# OpenEVSE_PLUS_v2_30a.net
KiCad netlist of a schematic drawn in EAGLE
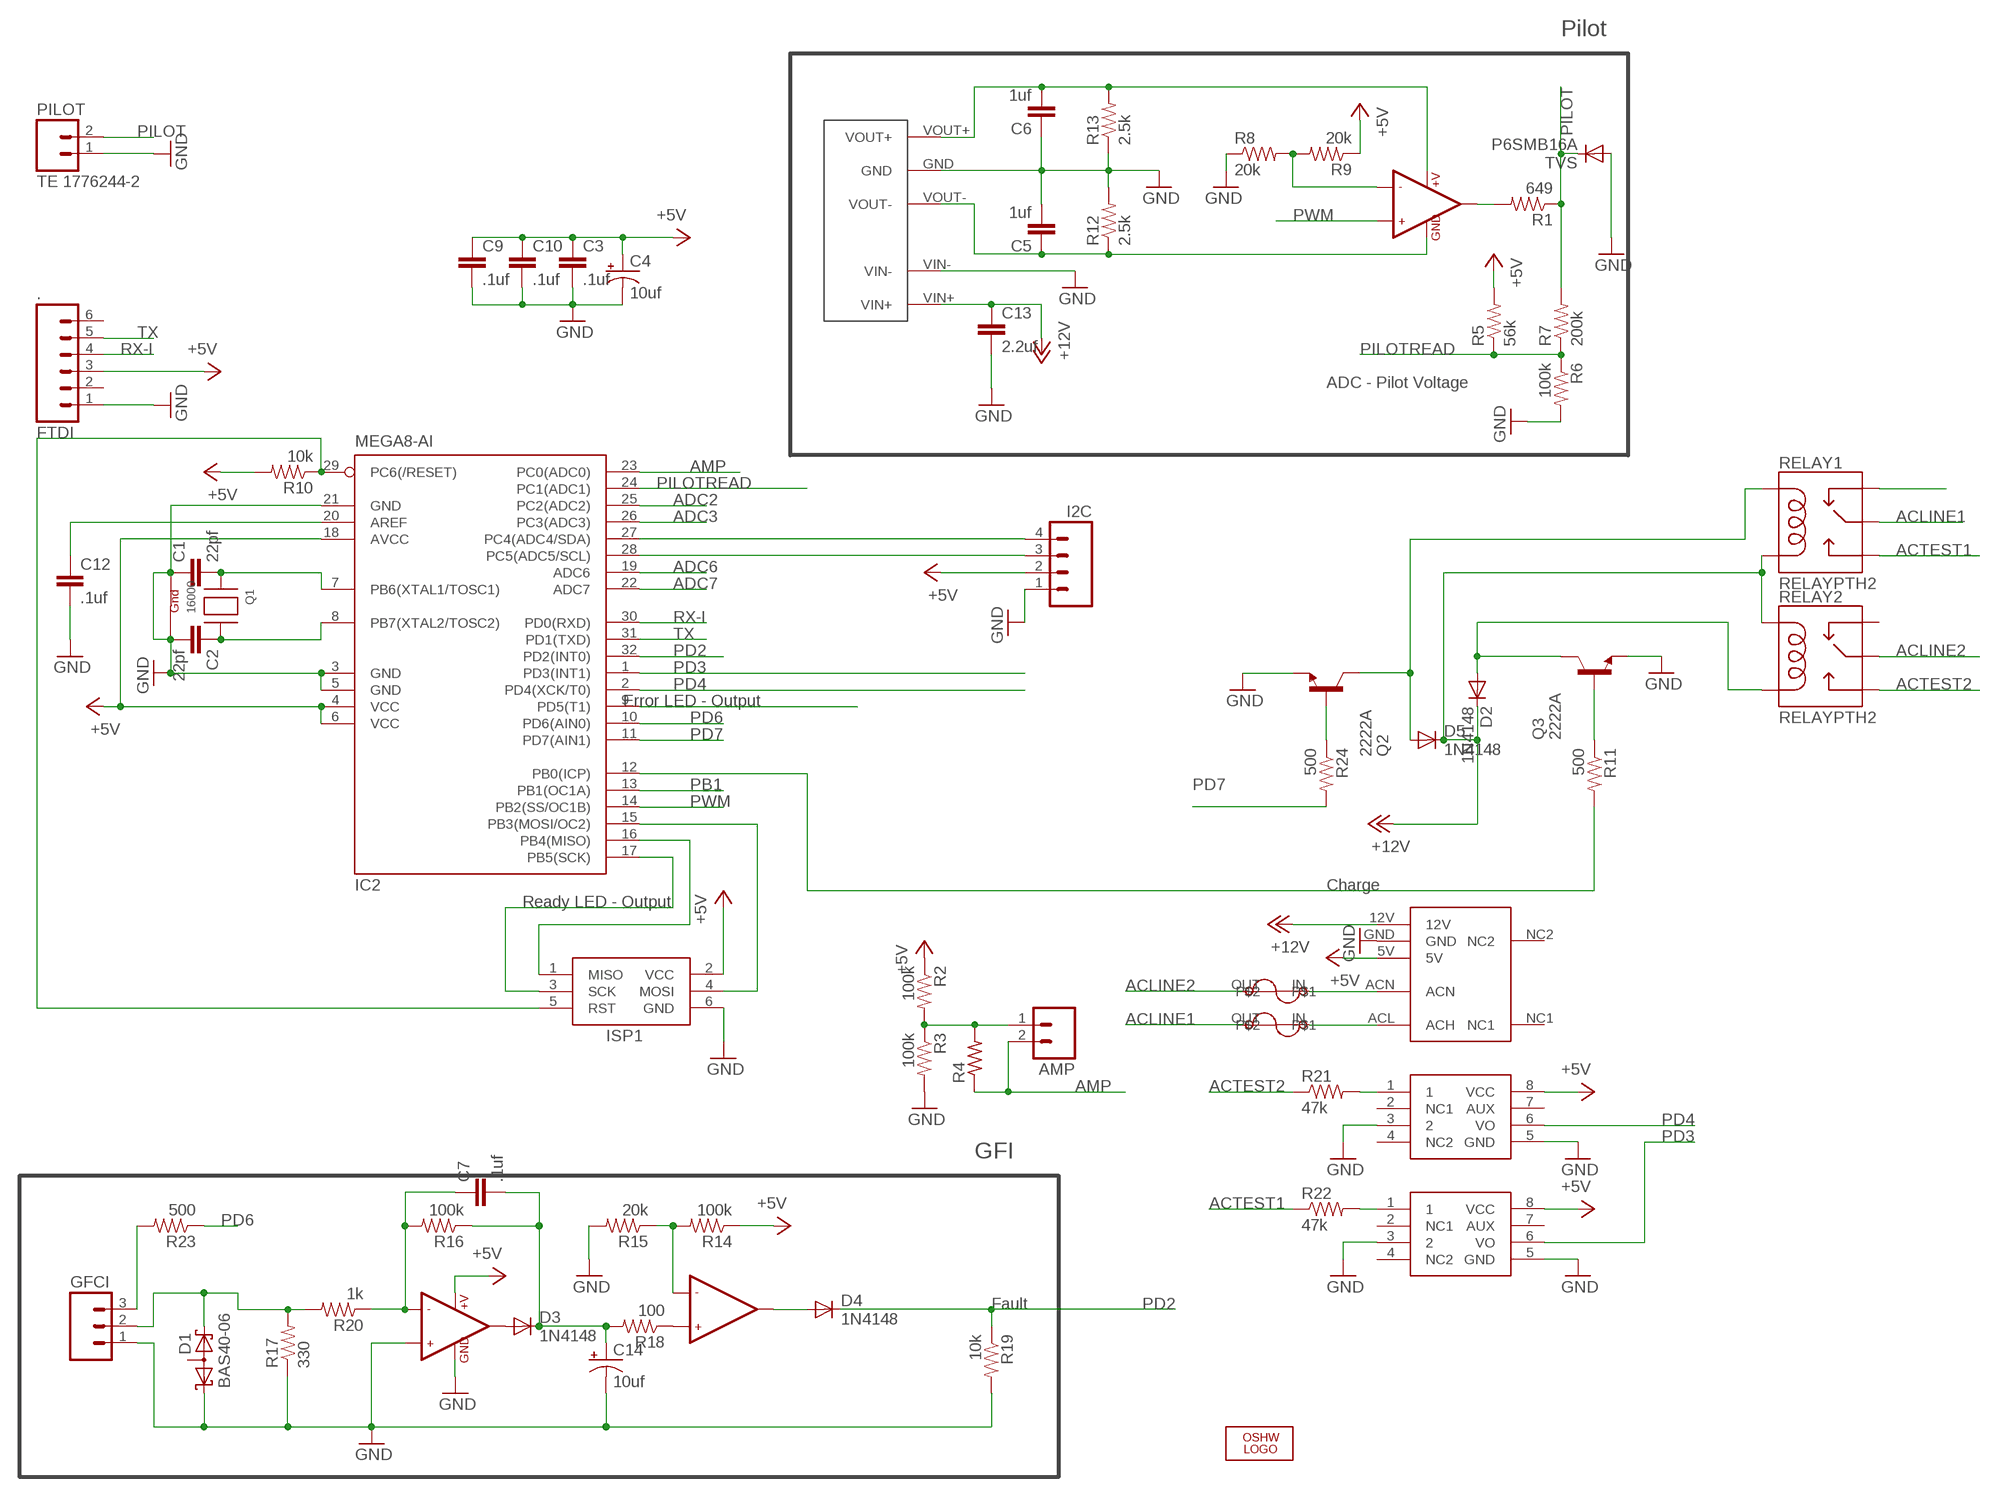
[diagram p0: schematic, sheet 1]

(export (version "E")
  (design (tool "Eeschema 10.0.6"))
  (components
    (comp (ref ".")
      (value "FTDI")
      (footprint "eagle-import:1X06_LOCK")
      (libsource (lib "eagle-import") (part "M06LOCK"))
    )
    (comp (ref "AMP")
      (value "M02LOCK")
      (footprint "eagle-import:1X02_LOCK")
      (libsource (lib "eagle-import") (part "M02LOCK"))
    )
    (comp (ref "C1")
      (value "22pf")
      (footprint "eagle-import:0805")
      (libsource (lib "eagle-import") (part "CAP0805"))
    )
    (comp (ref "C2")
      (value "22pf")
      (footprint "eagle-import:0805")
      (libsource (lib "eagle-import") (part "CAP0805"))
    )
    (comp (ref "C3")
      (value ".1uf")
      (footprint "eagle-import:0805")
      (libsource (lib "eagle-import") (part "CAP0805"))
    )
    (comp (ref "C4")
      (value "10uf")
      (footprint "eagle-import:EIA3216")
      (libsource (lib "eagle-import") (part "CAP_POL1206"))
    )
    (comp (ref "C5")
      (value "1uf")
      (footprint "eagle-import:0805")
      (libsource (lib "eagle-import") (part "CAP0805"))
    )
    (comp (ref "C6")
      (value "1uf")
      (footprint "eagle-import:0805")
      (libsource (lib "eagle-import") (part "CAP0805"))
    )
    (comp (ref "C7")
      (value ".1uf")
      (footprint "eagle-import:0805")
      (libsource (lib "eagle-import") (part "CAP0805"))
    )
    (comp (ref "C9")
      (value ".1uf")
      (footprint "eagle-import:0805")
      (libsource (lib "eagle-import") (part "CAP0805"))
    )
    (comp (ref "C10")
      (value ".1uf")
      (footprint "eagle-import:0805")
      (libsource (lib "eagle-import") (part "CAP0805"))
    )
    (comp (ref "C12")
      (value ".1uf")
      (footprint "eagle-import:0805")
      (libsource (lib "eagle-import") (part "CAP0805"))
    )
    (comp (ref "C13")
      (value "2.2uf")
      (footprint "eagle-import:0805")
      (libsource (lib "eagle-import") (part "CAP0805"))
    )
    (comp (ref "C14")
      (value "10uf")
      (footprint "eagle-import:EIA3216")
      (libsource (lib "eagle-import") (part "CAP_POL1206"))
    )
    (comp (ref "D1")
      (value "BAS40-06")
      (footprint "eagle-import:SOT23")
      (libsource (lib "eagle-import") (part "BAS40-06"))
    )
    (comp (ref "D2")
      (value "1N4148")
      (footprint "eagle-import:SOD123")
      (libsource (lib "eagle-import") (part "DIODE-SOD123"))
    )
    (comp (ref "D3")
      (value "1N4148")
      (footprint "eagle-import:SOD123")
      (libsource (lib "eagle-import") (part "DIODE-SOD123"))
    )
    (comp (ref "D4")
      (value "1N4148")
      (footprint "eagle-import:SOD123")
      (libsource (lib "eagle-import") (part "DIODE-SOD123"))
    )
    (comp (ref "D5")
      (value "1N4148")
      (footprint "eagle-import:SOD123")
      (libsource (lib "eagle-import") (part "DIODE-SOD123"))
    )
    (comp (ref "DCDC")
      (value "D107E")
      (footprint "eagle-import:DCDC_SIP")
      (libsource (lib "eagle-import") (part "DCDC_SIP"))
    )
    (comp (ref "GFCI")
      (value "M03LOCK")
      (footprint "eagle-import:1X03_LOCK")
      (libsource (lib "eagle-import") (part "M03LOCK"))
    )
    (comp (ref "I2C")
      (value "M04LOCK")
      (footprint "eagle-import:1X04_LOCK")
      (libsource (lib "eagle-import") (part "M04LOCK"))
    )
    (comp (ref "IC1")
      (value "MID400")
      (footprint "eagle-import:DIP08")
      (libsource (lib "eagle-import") (part "MID400"))
    )
    (comp (ref "IC2")
      (value "MEGA8-AI")
      (footprint "eagle-import:TQFP32-08")
      (fields (field (name "MPN") "ATMEGA8-16AU"))
      (libsource (lib "eagle-import") (part "MEGA8-AI"))
    )
    (comp (ref "IC3")
      (value "LMV358")
      (footprint "eagle-import:SO08")
      (libsource (lib "eagle-import") (part "LMV358"))
    )
    (comp (ref "IC4")
      (value "LMV358")
      (footprint "eagle-import:SO08")
      (libsource (lib "eagle-import") (part "LMV358"))
    )
    (comp (ref "IC5")
      (value "MID400")
      (footprint "eagle-import:DIP08")
      (libsource (lib "eagle-import") (part "MID400"))
    )
    (comp (ref "ISP1")
      (value "AVRISP-6")
      (footprint "eagle-import:AVRISP")
      (libsource (lib "eagle-import") (part "AVRISP-6"))
    )
    (comp (ref "LOGO1")
      (value "OSHW_LOGO_8MILX0150-NT")
      (footprint "eagle-import:OSHW_8X150_NOTEXT")
      (libsource (lib "eagle-import") (part "OSHW_LOGO_8MILX0150-NT"))
    )
    (comp (ref "PILOT")
      (value "TE 1776244-2")
      (footprint "eagle-import:SCREWTERMINAL-5MM-2")
      (libsource (lib "eagle-import") (part "M025MM"))
    )
    (comp (ref "Q1")
      (value "16000")
      (footprint "eagle-import:NX3225")
      (libsource (lib "eagle-import") (part "XTAL-4-3225"))
    )
    (comp (ref "Q2")
      (value "2222A")
      (footprint "eagle-import:SOT23")
      (libsource (lib "eagle-import") (part "BCX70SMD"))
    )
    (comp (ref "Q3")
      (value "2222A")
      (footprint "eagle-import:SOT23")
      (libsource (lib "eagle-import") (part "BCX70SMD"))
    )
    (comp (ref "R1")
      (value "649")
      (footprint "eagle-import:0805")
      (libsource (lib "eagle-import") (part "RESISTOR0805-RES"))
    )
    (comp (ref "R2")
      (value "100k")
      (footprint "eagle-import:0805")
      (libsource (lib "eagle-import") (part "RESISTOR0805-RES"))
    )
    (comp (ref "R3")
      (value "100k")
      (footprint "eagle-import:0805")
      (libsource (lib "eagle-import") (part "RESISTOR0805-RES"))
    )
    (comp (ref "R4")
      (value "R-US_0207/2V")
      (footprint "eagle-import:0207_2V")
      (libsource (lib "eagle-import") (part "R-US_0207/2V"))
    )
    (comp (ref "R5")
      (value "56k")
      (footprint "eagle-import:0805")
      (libsource (lib "eagle-import") (part "RESISTOR0805-RES"))
    )
    (comp (ref "R6")
      (value "100k")
      (footprint "eagle-import:0805")
      (libsource (lib "eagle-import") (part "RESISTOR0805-RES"))
    )
    (comp (ref "R7")
      (value "200k")
      (footprint "eagle-import:0805")
      (libsource (lib "eagle-import") (part "RESISTOR0805-RES"))
    )
    (comp (ref "R8")
      (value "20k")
      (footprint "eagle-import:0805")
      (libsource (lib "eagle-import") (part "RESISTOR0805-RES"))
    )
    (comp (ref "R9")
      (value "20k")
      (footprint "eagle-import:0805")
      (libsource (lib "eagle-import") (part "RESISTOR0805-RES"))
    )
    (comp (ref "R10")
      (value "10k")
      (footprint "eagle-import:0805")
      (libsource (lib "eagle-import") (part "RESISTOR0805-RES"))
    )
    (comp (ref "R11")
      (value "500")
      (footprint "eagle-import:0805")
      (libsource (lib "eagle-import") (part "RESISTOR0805-RES"))
    )
    (comp (ref "R12")
      (value "2.5k")
      (footprint "eagle-import:0805")
      (libsource (lib "eagle-import") (part "RESISTOR0805-RES"))
    )
    (comp (ref "R13")
      (value "2.5k")
      (footprint "eagle-import:0805")
      (libsource (lib "eagle-import") (part "RESISTOR0805-RES"))
    )
    (comp (ref "R14")
      (value "100k")
      (footprint "eagle-import:0805")
      (libsource (lib "eagle-import") (part "RESISTOR0805-RES"))
    )
    (comp (ref "R15")
      (value "20k")
      (footprint "eagle-import:0805")
      (libsource (lib "eagle-import") (part "RESISTOR0805-RES"))
    )
    (comp (ref "R16")
      (value "100k")
      (footprint "eagle-import:0805")
      (libsource (lib "eagle-import") (part "RESISTOR0805-RES"))
    )
    (comp (ref "R17")
      (value "330")
      (footprint "eagle-import:0805")
      (libsource (lib "eagle-import") (part "RESISTOR0805-RES"))
    )
    (comp (ref "R18")
      (value "100")
      (footprint "eagle-import:0805")
      (libsource (lib "eagle-import") (part "RESISTOR0805-RES"))
    )
    (comp (ref "R19")
      (value "10k")
      (footprint "eagle-import:0805")
      (libsource (lib "eagle-import") (part "RESISTOR0805-RES"))
    )
    (comp (ref "R20")
      (value "1k")
      (footprint "eagle-import:0805")
      (libsource (lib "eagle-import") (part "RESISTOR0805-RES"))
    )
    (comp (ref "R21")
      (value "47k")
      (footprint "eagle-import:AXIAL-0.4")
      (libsource (lib "eagle-import") (part "RESISTORPTH-1/4W"))
    )
    (comp (ref "R22")
      (value "47k")
      (footprint "eagle-import:AXIAL-0.4")
      (libsource (lib "eagle-import") (part "RESISTORPTH-1/4W"))
    )
    (comp (ref "R23")
      (value "500")
      (footprint "eagle-import:0805")
      (libsource (lib "eagle-import") (part "RESISTOR0805-RES"))
    )
    (comp (ref "R24")
      (value "500")
      (footprint "eagle-import:0805")
      (libsource (lib "eagle-import") (part "RESISTOR0805-RES"))
    )
    (comp (ref "RELAY1")
      (value "RELAYPTH2")
      (footprint "eagle-import:RELAY-T9A")
      (libsource (lib "eagle-import") (part "RELAYPTH2"))
    )
    (comp (ref "RELAY2")
      (value "RELAYPTH2")
      (footprint "eagle-import:RELAY-T9A")
      (libsource (lib "eagle-import") (part "RELAYPTH2"))
    )
    (comp (ref "TVS")
      (value "P6SMB16A")
      (footprint "eagle-import:SMB")
      (libsource (lib "eagle-import") (part "DIODE-SMB"))
    )
    (comp (ref "U$1")
      (value "MPM-04E-1205")
      (footprint "eagle-import:MPM-04E-1205")
      (libsource (lib "eagle-import") (part "MPM-04E-1205"))
    )
    (comp (ref "U$2")
      (value "BEL1AFUSE")
      (footprint "eagle-import:BELFUSE1A")
      (libsource (lib "eagle-import") (part "BEL1AFUSE"))
    )
    (comp (ref "U$5")
      (value "BEL1AFUSE")
      (footprint "eagle-import:BELFUSE1A")
      (libsource (lib "eagle-import") (part "BEL1AFUSE"))
    )
  )
  (nets
    (net (code "1") (name "+5V") (class "Default")
      (node (ref ".") (pin "3") (pinfunction "3_3") (pintype "passive"))
      (node (ref "C10") (pin "1") (pinfunction "1_1") (pintype "passive"))
      (node (ref "C3") (pin "1") (pinfunction "1_1") (pintype "passive"))
      (node (ref "C4") (pin "A") (pinfunction "+_A") (pintype "passive"))
      (node (ref "C9") (pin "1") (pinfunction "1_1") (pintype "passive"))
      (node (ref "I2C") (pin "2") (pinfunction "2_2") (pintype "passive"))
      (node (ref "IC1") (pin "8") (pinfunction "VCC_8") (pintype "bidirectional"))
      (node (ref "IC2") (pin "18") (pinfunction "AVCC_18") (pintype "power_in"))
      (node (ref "IC2") (pin "4") (pinfunction "VCC_4") (pintype "power_in"))
      (node (ref "IC2") (pin "6") (pinfunction "VCC_6") (pintype "power_in"))
      (node (ref "IC3") (pin "8") (pinfunction "+V_8") (pintype "power_in"))
      (node (ref "IC5") (pin "8") (pinfunction "VCC_8") (pintype "bidirectional"))
      (node (ref "ISP1") (pin "2") (pinfunction "VCC_2") (pintype "power_in"))
      (node (ref "R10") (pin "2") (pinfunction "2_2") (pintype "passive"))
      (node (ref "R14") (pin "1") (pinfunction "1_1") (pintype "passive"))
      (node (ref "R2") (pin "1") (pinfunction "1_1") (pintype "passive"))
      (node (ref "R5") (pin "2") (pinfunction "2_2") (pintype "passive"))
      (node (ref "R9") (pin "1") (pinfunction "1_1") (pintype "passive"))
      (node (ref "U$1") (pin "5V") (pinfunction "5V_5V") (pintype "bidirectional"))
    )
    (net (code "2") (name "+12V") (class "Default")
      (node (ref "C13") (pin "1") (pinfunction "1_1") (pintype "passive"))
      (node (ref "D2") (pin "C") (pinfunction "C_C") (pintype "passive"))
      (node (ref "D5") (pin "C") (pinfunction "C_C") (pintype "passive"))
      (node (ref "DCDC") (pin "VIN+") (pinfunction "VIN+_VIN+") (pintype "bidirectional"))
      (node (ref "RELAY1") (pin "COIL2") (pinfunction "COIL2_COIL2") (pintype "bidirectional"))
      (node (ref "RELAY2") (pin "COIL1") (pinfunction "COIL1_COIL1") (pintype "bidirectional"))
      (node (ref "U$1") (pin "12V") (pinfunction "12V_12V") (pintype "bidirectional"))
    )
    (net (code "3") (name "/ACLINE1") (class "Default")
      (node (ref "RELAY1") (pin "MAIN") (pinfunction "MAIN_MAIN") (pintype "bidirectional"))
      (node (ref "U$2") (pin "OUT") (pinfunction "P$1_OUT") (pintype "bidirectional"))
    )
    (net (code "4") (name "/ACLINE2") (class "Default")
      (node (ref "RELAY2") (pin "MAIN") (pinfunction "MAIN_MAIN") (pintype "bidirectional"))
      (node (ref "U$5") (pin "OUT") (pinfunction "P$1_OUT") (pintype "bidirectional"))
    )
    (net (code "5") (name "/ACTEST1") (class "Default")
      (node (ref "R22") (pin "P$1") (pinfunction "1_P$1") (pintype "passive"))
      (node (ref "RELAY1") (pin "NO") (pinfunction "NO_NO") (pintype "bidirectional"))
    )
    (net (code "6") (name "/ACTEST2") (class "Default")
      (node (ref "R21") (pin "P$1") (pinfunction "1_P$1") (pintype "passive"))
      (node (ref "RELAY2") (pin "NO") (pinfunction "NO_NO") (pintype "bidirectional"))
    )
    (net (code "7") (name "/ADC2") (class "Default")
      (node (ref "IC2") (pin "25") (pinfunction "PC2(ADC2)_25") (pintype "bidirectional"))
    )
    (net (code "8") (name "/ADC3") (class "Default")
      (node (ref "IC2") (pin "26") (pinfunction "PC3(ADC3)_26") (pintype "bidirectional"))
    )
    (net (code "9") (name "/ADC6") (class "Default")
      (node (ref "IC2") (pin "19") (pinfunction "ADC6_19") (pintype "bidirectional"))
    )
    (net (code "10") (name "/ADC7") (class "Default")
      (node (ref "IC2") (pin "22") (pinfunction "ADC7_22") (pintype "bidirectional"))
    )
    (net (code "11") (name "/AMP") (class "Default")
      (node (ref "AMP") (pin "2") (pinfunction "2_2") (pintype "passive"))
      (node (ref "IC2") (pin "23") (pinfunction "PC0(ADC0)_23") (pintype "bidirectional"))
      (node (ref "R4") (pin "1") (pinfunction "1_1") (pintype "passive"))
    )
    (net (code "12") (name "/PB1") (class "Default")
      (node (ref "IC2") (pin "13") (pinfunction "PB1(OC1A)_13") (pintype "bidirectional"))
    )
    (net (code "13") (name "/PD2") (class "Default")
      (node (ref "D4") (pin "C") (pinfunction "C_C") (pintype "passive"))
      (node (ref "IC2") (pin "32") (pinfunction "PD2(INT0)_32") (pintype "bidirectional"))
      (node (ref "R19") (pin "1") (pinfunction "1_1") (pintype "passive"))
    )
    (net (code "14") (name "/PD3") (class "Default")
      (node (ref "IC2") (pin "1") (pinfunction "PD3(INT1)_1") (pintype "bidirectional"))
      (node (ref "IC5") (pin "6") (pinfunction "VO_6") (pintype "bidirectional"))
    )
    (net (code "15") (name "/PD4") (class "Default")
      (node (ref "IC1") (pin "6") (pinfunction "VO_6") (pintype "bidirectional"))
      (node (ref "IC2") (pin "2") (pinfunction "PD4(XCK/T0)_2") (pintype "bidirectional"))
    )
    (net (code "16") (name "/PD6") (class "Default")
      (node (ref "IC2") (pin "10") (pinfunction "PD6(AIN0)_10") (pintype "bidirectional"))
      (node (ref "R23") (pin "1") (pinfunction "1_1") (pintype "passive"))
    )
    (net (code "17") (name "/PD7") (class "Default")
      (node (ref "IC2") (pin "11") (pinfunction "PD7(AIN1)_11") (pintype "bidirectional"))
      (node (ref "R24") (pin "2") (pinfunction "2_2") (pintype "passive"))
    )
    (net (code "18") (name "/PILOT") (class "Default")
      (node (ref "PILOT") (pin "2") (pinfunction "2_2") (pintype "passive"))
      (node (ref "R1") (pin "1") (pinfunction "1_1") (pintype "passive"))
      (node (ref "R7") (pin "2") (pinfunction "2_2") (pintype "passive"))
      (node (ref "TVS") (pin "C") (pinfunction "C_C") (pintype "passive"))
    )
    (net (code "19") (name "/PILOTREAD") (class "Default")
      (node (ref "IC2") (pin "24") (pinfunction "PC1(ADC1)_24") (pintype "bidirectional"))
      (node (ref "R5") (pin "1") (pinfunction "1_1") (pintype "passive"))
      (node (ref "R6") (pin "1") (pinfunction "1_1") (pintype "passive"))
      (node (ref "R7") (pin "1") (pinfunction "1_1") (pintype "passive"))
    )
    (net (code "20") (name "/PWM") (class "Default")
      (node (ref "IC2") (pin "14") (pinfunction "PB2(SS/OC1B)_14") (pintype "bidirectional"))
      (node (ref "IC4") (pin "3") (pinfunction "+IN1_3") (pintype "input"))
    )
    (net (code "21") (name "/RX-I") (class "Default")
      (node (ref ".") (pin "4") (pinfunction "4_4") (pintype "passive"))
      (node (ref "IC2") (pin "30") (pinfunction "PD0(RXD)_30") (pintype "bidirectional"))
    )
    (net (code "22") (name "/TX") (class "Default")
      (node (ref ".") (pin "5") (pinfunction "5_5") (pintype "passive"))
      (node (ref "IC2") (pin "31") (pinfunction "PD1(TXD)_31") (pintype "bidirectional"))
    )
    (net (code "23") (name "GND") (class "Default")
      (node (ref ".") (pin "1") (pinfunction "1_1") (pintype "passive"))
      (node (ref "C1") (pin "1") (pinfunction "1_1") (pintype "passive"))
      (node (ref "C10") (pin "2") (pinfunction "2_2") (pintype "passive"))
      (node (ref "C12") (pin "2") (pinfunction "2_2") (pintype "passive"))
      (node (ref "C13") (pin "2") (pinfunction "2_2") (pintype "passive"))
      (node (ref "C14") (pin "C") (pinfunction "-_C") (pintype "passive"))
      (node (ref "C2") (pin "2") (pinfunction "2_2") (pintype "passive"))
      (node (ref "C3") (pin "2") (pinfunction "2_2") (pintype "passive"))
      (node (ref "C4") (pin "C") (pinfunction "-_C") (pintype "passive"))
      (node (ref "C5") (pin "2") (pinfunction "2_2") (pintype "passive"))
      (node (ref "C6") (pin "1") (pinfunction "1_1") (pintype "passive"))
      (node (ref "C9") (pin "2") (pinfunction "2_2") (pintype "passive"))
      (node (ref "D1") (pin "1") (pinfunction "K1_1") (pintype "passive"))
      (node (ref "DCDC") (pin "GND") (pinfunction "GND_GND") (pintype "bidirectional"))
      (node (ref "DCDC") (pin "VIN-") (pinfunction "VIN-_VIN-") (pintype "bidirectional"))
      (node (ref "GFCI") (pin "1") (pinfunction "1_1") (pintype "passive"))
      (node (ref "I2C") (pin "1") (pinfunction "1_1") (pintype "passive"))
      (node (ref "IC1") (pin "3") (pinfunction "2_3") (pintype "bidirectional"))
      (node (ref "IC1") (pin "5") (pinfunction "GND_5") (pintype "bidirectional"))
      (node (ref "IC2") (pin "21") (pinfunction "GND_21") (pintype "power_in"))
      (node (ref "IC2") (pin "3") (pinfunction "GND_3") (pintype "power_in"))
      (node (ref "IC2") (pin "5") (pinfunction "GND_5") (pintype "power_in"))
      (node (ref "IC3") (pin "3") (pinfunction "+IN1_3") (pintype "input"))
      (node (ref "IC3") (pin "4") (pinfunction "GND_4") (pintype "power_in"))
      (node (ref "IC5") (pin "3") (pinfunction "2_3") (pintype "bidirectional"))
      (node (ref "IC5") (pin "5") (pinfunction "GND_5") (pintype "bidirectional"))
      (node (ref "ISP1") (pin "6") (pinfunction "GND_6") (pintype "power_in"))
      (node (ref "PILOT") (pin "1") (pinfunction "1_1") (pintype "passive"))
      (node (ref "Q1") (pin "1") (pinfunction "G1_1") (pintype "power_in"))
      (node (ref "Q1") (pin "3") (pinfunction "G2_3") (pintype "power_in"))
      (node (ref "Q2") (pin "2") (pinfunction "E_2") (pintype "passive"))
      (node (ref "Q3") (pin "2") (pinfunction "E_2") (pintype "passive"))
      (node (ref "R12") (pin "2") (pinfunction "2_2") (pintype "passive"))
      (node (ref "R13") (pin "1") (pinfunction "1_1") (pintype "passive"))
      (node (ref "R15") (pin "2") (pinfunction "2_2") (pintype "passive"))
      (node (ref "R17") (pin "1") (pinfunction "1_1") (pintype "passive"))
      (node (ref "R19") (pin "2") (pinfunction "2_2") (pintype "passive"))
      (node (ref "R3") (pin "2") (pinfunction "2_2") (pintype "passive"))
      (node (ref "R6") (pin "2") (pinfunction "2_2") (pintype "passive"))
      (node (ref "R8") (pin "1") (pinfunction "1_1") (pintype "passive"))
      (node (ref "TVS") (pin "A") (pinfunction "A_A") (pintype "passive"))
      (node (ref "U$1") (pin "GND") (pinfunction "GND_GND") (pintype "bidirectional"))
    )
    (net (code "24") (name "Net-(AMP-Pad1)") (class "Default")
      (node (ref "AMP") (pin "1") (pinfunction "1_1") (pintype "passive"))
      (node (ref "R2") (pin "2") (pinfunction "2_2") (pintype "passive"))
      (node (ref "R3") (pin "1") (pinfunction "1_1") (pintype "passive"))
      (node (ref "R4") (pin "2") (pinfunction "2_2") (pintype "passive"))
    )
    (net (code "25") (name "Net-(C14-+)") (class "Default")
      (node (ref "C14") (pin "A") (pinfunction "+_A") (pintype "passive"))
      (node (ref "C7") (pin "2") (pinfunction "2_2") (pintype "passive"))
      (node (ref "D3") (pin "C") (pinfunction "C_C") (pintype "passive"))
      (node (ref "R16") (pin "1") (pinfunction "1_1") (pintype "passive"))
      (node (ref "R18") (pin "2") (pinfunction "2_2") (pintype "passive"))
    )
    (net (code "26") (name "Net-(D1-K2)") (class "Default")
      (node (ref "D1") (pin "2") (pinfunction "K2_2") (pintype "passive"))
      (node (ref "GFCI") (pin "2") (pinfunction "2_2") (pintype "passive"))
      (node (ref "R17") (pin "2") (pinfunction "2_2") (pintype "passive"))
      (node (ref "R20") (pin "2") (pinfunction "2_2") (pintype "passive"))
    )
    (net (code "27") (name "Net-(GFCI-Pad3)") (class "Default")
      (node (ref "GFCI") (pin "3") (pinfunction "3_3") (pintype "passive"))
      (node (ref "R23") (pin "2") (pinfunction "2_2") (pintype "passive"))
    )
    (net (code "28") (name "Net-(IC2-AREF)") (class "Default")
      (node (ref "C12") (pin "1") (pinfunction "1_1") (pintype "passive"))
      (node (ref "IC2") (pin "20") (pinfunction "AREF_20") (pintype "passive"))
    )
    (net (code "29") (name "Net-(IC2-PB0(ICP))") (class "Default")
      (node (ref "IC2") (pin "12") (pinfunction "PB0(ICP)_12") (pintype "bidirectional"))
      (node (ref "R11") (pin "2") (pinfunction "2_2") (pintype "passive"))
    )
    (net (code "30") (name "Net-(IC2-PB3(MOSI{slash}OC2))") (class "Default")
      (node (ref "IC2") (pin "15") (pinfunction "PB3(MOSI/OC2)_15") (pintype "bidirectional"))
      (node (ref "ISP1") (pin "4") (pinfunction "MOSI_4") (pintype "output"))
    )
    (net (code "31") (name "Net-(IC2-PB4(MISO))") (class "Default")
      (node (ref "IC2") (pin "16") (pinfunction "PB4(MISO)_16") (pintype "bidirectional"))
      (node (ref "ISP1") (pin "1") (pinfunction "MISO_1") (pintype "input"))
    )
    (net (code "32") (name "Net-(IC2-PB5(SCK))") (class "Default")
      (node (ref "IC2") (pin "17") (pinfunction "PB5(SCK)_17") (pintype "bidirectional"))
      (node (ref "ISP1") (pin "3") (pinfunction "SCK_3") (pintype "output"))
    )
    (net (code "33") (name "Net-(IC2-PB6(XTAL1{slash}TOSC1))") (class "Default")
      (node (ref "C1") (pin "2") (pinfunction "2_2") (pintype "passive"))
      (node (ref "IC2") (pin "7") (pinfunction "PB6(XTAL1/TOSC1)_7") (pintype "bidirectional"))
      (node (ref "Q1") (pin "2") (pinfunction "X1_2") (pintype "bidirectional"))
    )
    (net (code "34") (name "Net-(IC2-PB7(XTAL2{slash}TOSC2))") (class "Default")
      (node (ref "C2") (pin "1") (pinfunction "1_1") (pintype "passive"))
      (node (ref "IC2") (pin "8") (pinfunction "PB7(XTAL2/TOSC2)_8") (pintype "bidirectional"))
      (node (ref "Q1") (pin "4") (pinfunction "X2_4") (pintype "bidirectional"))
    )
    (net (code "35") (name "Net-(IC2-PC4(ADC4{slash}SDA))") (class "Default")
      (node (ref "I2C") (pin "4") (pinfunction "4_4") (pintype "passive"))
      (node (ref "IC2") (pin "27") (pinfunction "PC4(ADC4/SDA)_27") (pintype "bidirectional"))
    )
    (net (code "36") (name "Net-(IC2-PC5(ADC5{slash}SCL))") (class "Default")
      (node (ref "I2C") (pin "3") (pinfunction "3_3") (pintype "passive"))
      (node (ref "IC2") (pin "28") (pinfunction "PC5(ADC5/SCL)_28") (pintype "bidirectional"))
    )
    (net (code "37") (name "Net-(IC2-PC6({slash}RESET))") (class "Default")
      (node (ref "IC2") (pin "29") (pinfunction "PC6(/RESET)_29") (pintype "bidirectional"))
      (node (ref "ISP1") (pin "5") (pinfunction "RST_5") (pintype "output"))
      (node (ref "R10") (pin "1") (pinfunction "1_1") (pintype "passive"))
    )
    (net (code "38") (name "Net-(IC3A--IN1)") (class "Default")
      (node (ref "C7") (pin "1") (pinfunction "1_1") (pintype "passive"))
      (node (ref "IC3") (pin "2") (pinfunction "-IN1_2") (pintype "input"))
      (node (ref "R16") (pin "2") (pinfunction "2_2") (pintype "passive"))
      (node (ref "R20") (pin "1") (pinfunction "1_1") (pintype "passive"))
    )
    (net (code "39") (name "Net-(IC3A-OUT1)") (class "Default")
      (node (ref "D3") (pin "A") (pinfunction "A_A") (pintype "passive"))
      (node (ref "IC3") (pin "1") (pinfunction "OUT1_1") (pintype "output"))
    )
    (net (code "40") (name "Net-(IC3B-+IN2)") (class "Default")
      (node (ref "IC3") (pin "5") (pinfunction "+IN2_5") (pintype "input"))
      (node (ref "R18") (pin "1") (pinfunction "1_1") (pintype "passive"))
    )
    (net (code "41") (name "Net-(IC3B--IN2)") (class "Default")
      (node (ref "IC3") (pin "6") (pinfunction "-IN2_6") (pintype "input"))
      (node (ref "R14") (pin "2") (pinfunction "2_2") (pintype "passive"))
      (node (ref "R15") (pin "1") (pinfunction "1_1") (pintype "passive"))
    )
    (net (code "42") (name "Net-(IC3B-OUT2)") (class "Default")
      (node (ref "D4") (pin "A") (pinfunction "A_A") (pintype "passive"))
      (node (ref "IC3") (pin "7") (pinfunction "OUT2_7") (pintype "output"))
    )
    (net (code "43") (name "Net-(IC4A-+V)") (class "Default")
      (node (ref "C6") (pin "2") (pinfunction "2_2") (pintype "passive"))
      (node (ref "DCDC") (pin "VOUT+") (pinfunction "VOUT+_VOUT+") (pintype "bidirectional"))
      (node (ref "IC4") (pin "8") (pinfunction "+V_8") (pintype "power_in"))
      (node (ref "R13") (pin "2") (pinfunction "2_2") (pintype "passive"))
    )
    (net (code "44") (name "Net-(IC4A--IN1)") (class "Default")
      (node (ref "IC4") (pin "2") (pinfunction "-IN1_2") (pintype "input"))
      (node (ref "R8") (pin "2") (pinfunction "2_2") (pintype "passive"))
      (node (ref "R9") (pin "2") (pinfunction "2_2") (pintype "passive"))
    )
    (net (code "45") (name "Net-(IC4A-GND)") (class "Default")
      (node (ref "C5") (pin "1") (pinfunction "1_1") (pintype "passive"))
      (node (ref "DCDC") (pin "VOUT-") (pinfunction "VOUT-_VOUT-") (pintype "bidirectional"))
      (node (ref "IC4") (pin "4") (pinfunction "GND_4") (pintype "power_in"))
      (node (ref "R12") (pin "1") (pinfunction "1_1") (pintype "passive"))
    )
    (net (code "46") (name "Net-(IC4A-OUT1)") (class "Default")
      (node (ref "IC4") (pin "1") (pinfunction "OUT1_1") (pintype "output"))
      (node (ref "R1") (pin "2") (pinfunction "2_2") (pintype "passive"))
    )
    (net (code "47") (name "Net-(Q2-B)") (class "Default")
      (node (ref "Q2") (pin "1") (pinfunction "B_1") (pintype "passive"))
      (node (ref "R24") (pin "1") (pinfunction "1_1") (pintype "passive"))
    )
    (net (code "48") (name "Net-(Q2-C)") (class "Default")
      (node (ref "D5") (pin "A") (pinfunction "A_A") (pintype "passive"))
      (node (ref "Q2") (pin "3") (pinfunction "C_3") (pintype "passive"))
      (node (ref "RELAY1") (pin "COIL1") (pinfunction "COIL1_COIL1") (pintype "bidirectional"))
    )
    (net (code "49") (name "Net-(Q3-B)") (class "Default")
      (node (ref "Q3") (pin "1") (pinfunction "B_1") (pintype "passive"))
      (node (ref "R11") (pin "1") (pinfunction "1_1") (pintype "passive"))
    )
    (net (code "50") (name "Net-(Q3-C)") (class "Default")
      (node (ref "D2") (pin "A") (pinfunction "A_A") (pintype "passive"))
      (node (ref "Q3") (pin "3") (pinfunction "C_3") (pintype "passive"))
      (node (ref "RELAY2") (pin "COIL2") (pinfunction "COIL2_COIL2") (pintype "bidirectional"))
    )
    (net (code "51") (name "Net-(R21-2)") (class "Default")
      (node (ref "IC1") (pin "1") (pinfunction "1_1") (pintype "bidirectional"))
      (node (ref "R21") (pin "P$2") (pinfunction "2_P$2") (pintype "passive"))
    )
    (net (code "52") (name "Net-(R22-2)") (class "Default")
      (node (ref "IC5") (pin "1") (pinfunction "1_1") (pintype "bidirectional"))
      (node (ref "R22") (pin "P$2") (pinfunction "2_P$2") (pintype "passive"))
    )
    (net (code "53") (name "Net-(U$1-ACH)") (class "Default")
      (node (ref "U$1") (pin "ACL") (pinfunction "ACH_ACL") (pintype "bidirectional"))
      (node (ref "U$2") (pin "IN") (pinfunction "P$2_IN") (pintype "bidirectional"))
    )
    (net (code "54") (name "Net-(U$5-P$2)") (class "Default")
      (node (ref "U$1") (pin "ACN") (pinfunction "ACN_ACN") (pintype "bidirectional"))
      (node (ref "U$5") (pin "IN") (pinfunction "P$2_IN") (pintype "bidirectional"))
    )
    (net (code "55") (name "unconnected-(.-Pad2)") (class "Default")
      (node (ref ".") (pin "2") (pinfunction "2_2") (pintype "passive"))
    )
    (net (code "56") (name "unconnected-(.-Pad6)") (class "Default")
      (node (ref ".") (pin "6") (pinfunction "6_6") (pintype "passive"))
    )
    (net (code "57") (name "unconnected-(D1-AA-Pad3)") (class "Default")
      (node (ref "D1") (pin "3") (pinfunction "AA_3") (pintype "passive"))
    )
    (net (code "58") (name "unconnected-(IC1-AUX-Pad7)") (class "Default")
      (node (ref "IC1") (pin "7") (pinfunction "AUX_7") (pintype "bidirectional"))
    )
    (net (code "59") (name "unconnected-(IC1-NC1-Pad2)") (class "Default")
      (node (ref "IC1") (pin "2") (pinfunction "NC1_2") (pintype "bidirectional"))
    )
    (net (code "60") (name "unconnected-(IC1-NC2-Pad4)") (class "Default")
      (node (ref "IC1") (pin "4") (pinfunction "NC2_4") (pintype "bidirectional"))
    )
    (net (code "61") (name "unconnected-(IC2-PD5(T1)-Pad9)") (class "Default")
      (node (ref "IC2") (pin "9") (pinfunction "PD5(T1)_9") (pintype "bidirectional"))
    )
    (net (code "62") (name "unconnected-(IC5-AUX-Pad7)") (class "Default")
      (node (ref "IC5") (pin "7") (pinfunction "AUX_7") (pintype "bidirectional"))
    )
    (net (code "63") (name "unconnected-(IC5-NC1-Pad2)") (class "Default")
      (node (ref "IC5") (pin "2") (pinfunction "NC1_2") (pintype "bidirectional"))
    )
    (net (code "64") (name "unconnected-(IC5-NC2-Pad4)") (class "Default")
      (node (ref "IC5") (pin "4") (pinfunction "NC2_4") (pintype "bidirectional"))
    )
    (net (code "65") (name "unconnected-(RELAY1-PadNC)") (class "Default")
      (node (ref "RELAY1") (pin "NC") (pinfunction "NC_NC") (pintype "bidirectional"))
    )
    (net (code "66") (name "unconnected-(RELAY2-PadNC)") (class "Default")
      (node (ref "RELAY2") (pin "NC") (pinfunction "NC_NC") (pintype "bidirectional"))
    )
    (net (code "67") (name "unconnected-(U$1-PadNC1)") (class "Default")
      (node (ref "U$1") (pin "NC1") (pinfunction "NC1_NC1") (pintype "bidirectional"))
    )
    (net (code "68") (name "unconnected-(U$1-PadNC2)") (class "Default")
      (node (ref "U$1") (pin "NC2") (pinfunction "NC2_NC2") (pintype "bidirectional"))
    )
  )
)
